# 165AMP_NG_V2.net
KiCad netlist of a schematic drawn in EAGLE
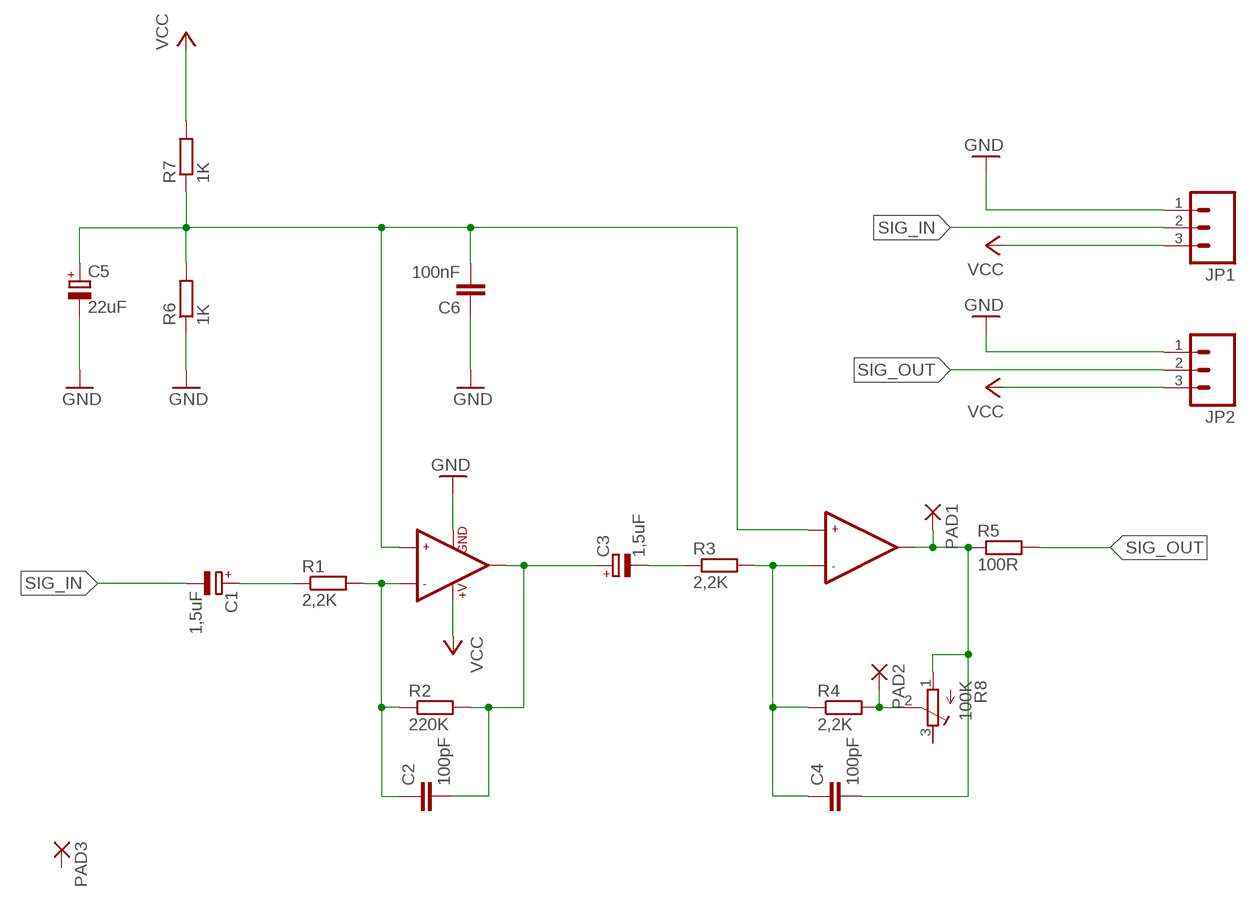
[diagram p0: schematic, sheet 1]

(export (version "E")
  (design (tool "Eeschema 10.0.6"))
  (components
    (comp (ref "C1")
      (value "1,5uF")
      (footprint "eagle-import:CT6032")
      (libsource (lib "eagle-import") (part "CPOL-EUCT6032"))
    )
    (comp (ref "C2")
      (value "100pF")
      (footprint "eagle-import:C0805")
      (libsource (lib "eagle-import") (part "C-EUC0805"))
    )
    (comp (ref "C3")
      (value "1,5uF")
      (footprint "eagle-import:CT6032")
      (libsource (lib "eagle-import") (part "CPOL-EUCT6032"))
    )
    (comp (ref "C4")
      (value "100pF")
      (footprint "eagle-import:C0805")
      (libsource (lib "eagle-import") (part "C-EUC0805"))
    )
    (comp (ref "C5")
      (value "22uF")
      (footprint "eagle-import:CT6032")
      (libsource (lib "eagle-import") (part "CPOL-EUCT6032"))
    )
    (comp (ref "C6")
      (value "100nF")
      (footprint "eagle-import:C0805")
      (libsource (lib "eagle-import") (part "C-EUC0805"))
    )
    (comp (ref "IC1")
      (value "LMV358")
      (footprint "eagle-import:SO08")
      (libsource (lib "eagle-import") (part "LMV358"))
    )
    (comp (ref "JP1")
      (value "M03PTH")
      (footprint "eagle-import:1X03")
      (libsource (lib "eagle-import") (part "M03PTH"))
    )
    (comp (ref "JP2")
      (value "M03PTH")
      (footprint "eagle-import:1X03")
      (libsource (lib "eagle-import") (part "M03PTH"))
    )
    (comp (ref "PAD1")
      (value "1,6/0,8")
      (footprint "eagle-import:1,6_0,8")
      (libsource (lib "eagle-import") (part "1,6/0,8"))
    )
    (comp (ref "PAD2")
      (value "1,6/0,8")
      (footprint "eagle-import:1,6_0,8")
      (libsource (lib "eagle-import") (part "1,6/0,8"))
    )
    (comp (ref "PAD3")
      (value "1,6/0,8")
      (footprint "eagle-import:1,6_0,8")
      (libsource (lib "eagle-import") (part "1,6/0,8"))
    )
    (comp (ref "R1")
      (value "2,2K")
      (footprint "eagle-import:R1206")
      (libsource (lib "eagle-import") (part "R-EU_R1206"))
    )
    (comp (ref "R2")
      (value "220K")
      (footprint "eagle-import:R1206")
      (libsource (lib "eagle-import") (part "R-EU_R1206"))
    )
    (comp (ref "R3")
      (value "2,2K")
      (footprint "eagle-import:R1206")
      (libsource (lib "eagle-import") (part "R-EU_R1206"))
    )
    (comp (ref "R4")
      (value "2,2K")
      (footprint "eagle-import:R1206")
      (libsource (lib "eagle-import") (part "R-EU_R1206"))
    )
    (comp (ref "R5")
      (value "100R")
      (footprint "eagle-import:R1206")
      (libsource (lib "eagle-import") (part "R-EU_R1206"))
    )
    (comp (ref "R6")
      (value "1K")
      (footprint "eagle-import:R1206")
      (libsource (lib "eagle-import") (part "R-EU_R1206"))
    )
    (comp (ref "R7")
      (value "1K")
      (footprint "eagle-import:R1206")
      (libsource (lib "eagle-import") (part "R-EU_R1206"))
    )
    (comp (ref "R8")
      (value "100K")
      (footprint "eagle-import:RTRIMTS63Z")
      (libsource (lib "eagle-import") (part "R-TRIMMTS63Z"))
    )
  )
  (nets
    (net (code "1") (name "GND") (class "Default")
      (node (ref "C5") (pin "-") (pinfunction "-_-") (pintype "passive"))
      (node (ref "C6") (pin "1") (pinfunction "1_1") (pintype "passive"))
      (node (ref "IC1") (pin "4") (pinfunction "GND_4") (pintype "power_in"))
      (node (ref "JP1") (pin "1") (pinfunction "1_1") (pintype "passive"))
      (node (ref "JP2") (pin "1") (pinfunction "1_1") (pintype "passive"))
      (node (ref "R6") (pin "1") (pinfunction "1_1") (pintype "passive"))
    )
    (net (code "2") (name "Net-(C1-Pad+)") (class "Default")
      (node (ref "C1") (pin "+") (pinfunction "+_+") (pintype "passive"))
      (node (ref "R1") (pin "1") (pinfunction "1_1") (pintype "passive"))
    )
    (net (code "3") (name "Net-(C3-Pad-)") (class "Default")
      (node (ref "C3") (pin "-") (pinfunction "-_-") (pintype "passive"))
      (node (ref "R3") (pin "1") (pinfunction "1_1") (pintype "passive"))
    )
    (net (code "4") (name "Net-(IC1A-+IN1)") (class "Default")
      (node (ref "C5") (pin "+") (pinfunction "+_+") (pintype "passive"))
      (node (ref "C6") (pin "2") (pinfunction "2_2") (pintype "passive"))
      (node (ref "IC1") (pin "3") (pinfunction "+IN1_3") (pintype "input"))
      (node (ref "IC1") (pin "5") (pinfunction "+IN2_5") (pintype "input"))
      (node (ref "R6") (pin "2") (pinfunction "2_2") (pintype "passive"))
      (node (ref "R7") (pin "1") (pinfunction "1_1") (pintype "passive"))
    )
    (net (code "5") (name "Net-(IC1A--IN1)") (class "Default")
      (node (ref "C2") (pin "1") (pinfunction "1_1") (pintype "passive"))
      (node (ref "IC1") (pin "2") (pinfunction "-IN1_2") (pintype "input"))
      (node (ref "R1") (pin "2") (pinfunction "2_2") (pintype "passive"))
      (node (ref "R2") (pin "1") (pinfunction "1_1") (pintype "passive"))
    )
    (net (code "6") (name "Net-(IC1A-OUT1)") (class "Default")
      (node (ref "C2") (pin "2") (pinfunction "2_2") (pintype "passive"))
      (node (ref "C3") (pin "+") (pinfunction "+_+") (pintype "passive"))
      (node (ref "IC1") (pin "1") (pinfunction "OUT1_1") (pintype "output"))
      (node (ref "R2") (pin "2") (pinfunction "2_2") (pintype "passive"))
    )
    (net (code "7") (name "Net-(IC1B--IN2)") (class "Default")
      (node (ref "C4") (pin "1") (pinfunction "1_1") (pintype "passive"))
      (node (ref "IC1") (pin "6") (pinfunction "-IN2_6") (pintype "input"))
      (node (ref "R3") (pin "2") (pinfunction "2_2") (pintype "passive"))
      (node (ref "R4") (pin "1") (pinfunction "1_1") (pintype "passive"))
    )
    (net (code "8") (name "Net-(IC1B-OUT2)") (class "Default")
      (node (ref "C4") (pin "2") (pinfunction "2_2") (pintype "passive"))
      (node (ref "IC1") (pin "7") (pinfunction "OUT2_7") (pintype "output"))
      (node (ref "PAD1") (pin "1") (pinfunction "P_1") (pintype "passive"))
      (node (ref "R5") (pin "1") (pinfunction "1_1") (pintype "passive"))
      (node (ref "R8") (pin "1") (pinfunction "E_1") (pintype "passive"))
    )
    (net (code "9") (name "Net-(PAD2-P)") (class "Default")
      (node (ref "PAD2") (pin "1") (pinfunction "P_1") (pintype "passive"))
      (node (ref "R4") (pin "2") (pinfunction "2_2") (pintype "passive"))
      (node (ref "R8") (pin "2") (pinfunction "S_2") (pintype "passive"))
    )
    (net (code "10") (name "SIG_IN") (class "Default")
      (node (ref "C1") (pin "-") (pinfunction "-_-") (pintype "passive"))
      (node (ref "JP1") (pin "2") (pinfunction "2_2") (pintype "passive"))
    )
    (net (code "11") (name "SIG_OUT") (class "Default")
      (node (ref "JP2") (pin "2") (pinfunction "2_2") (pintype "passive"))
      (node (ref "R5") (pin "2") (pinfunction "2_2") (pintype "passive"))
    )
    (net (code "12") (name "VCC") (class "Default")
      (node (ref "IC1") (pin "8") (pinfunction "+V_8") (pintype "power_in"))
      (node (ref "JP1") (pin "3") (pinfunction "3_3") (pintype "passive"))
      (node (ref "JP2") (pin "3") (pinfunction "3_3") (pintype "passive"))
      (node (ref "R7") (pin "2") (pinfunction "2_2") (pintype "passive"))
    )
    (net (code "13") (name "unconnected-(PAD3-P-Pad1)") (class "Default")
      (node (ref "PAD3") (pin "1") (pinfunction "P_1") (pintype "passive"))
    )
    (net (code "14") (name "unconnected-(R8-A-Pad3)") (class "Default")
      (node (ref "R8") (pin "3") (pinfunction "A_3") (pintype "passive"))
    )
  )
)
